# imu_node.net
KiCad netlist of a schematic drawn in EAGLE
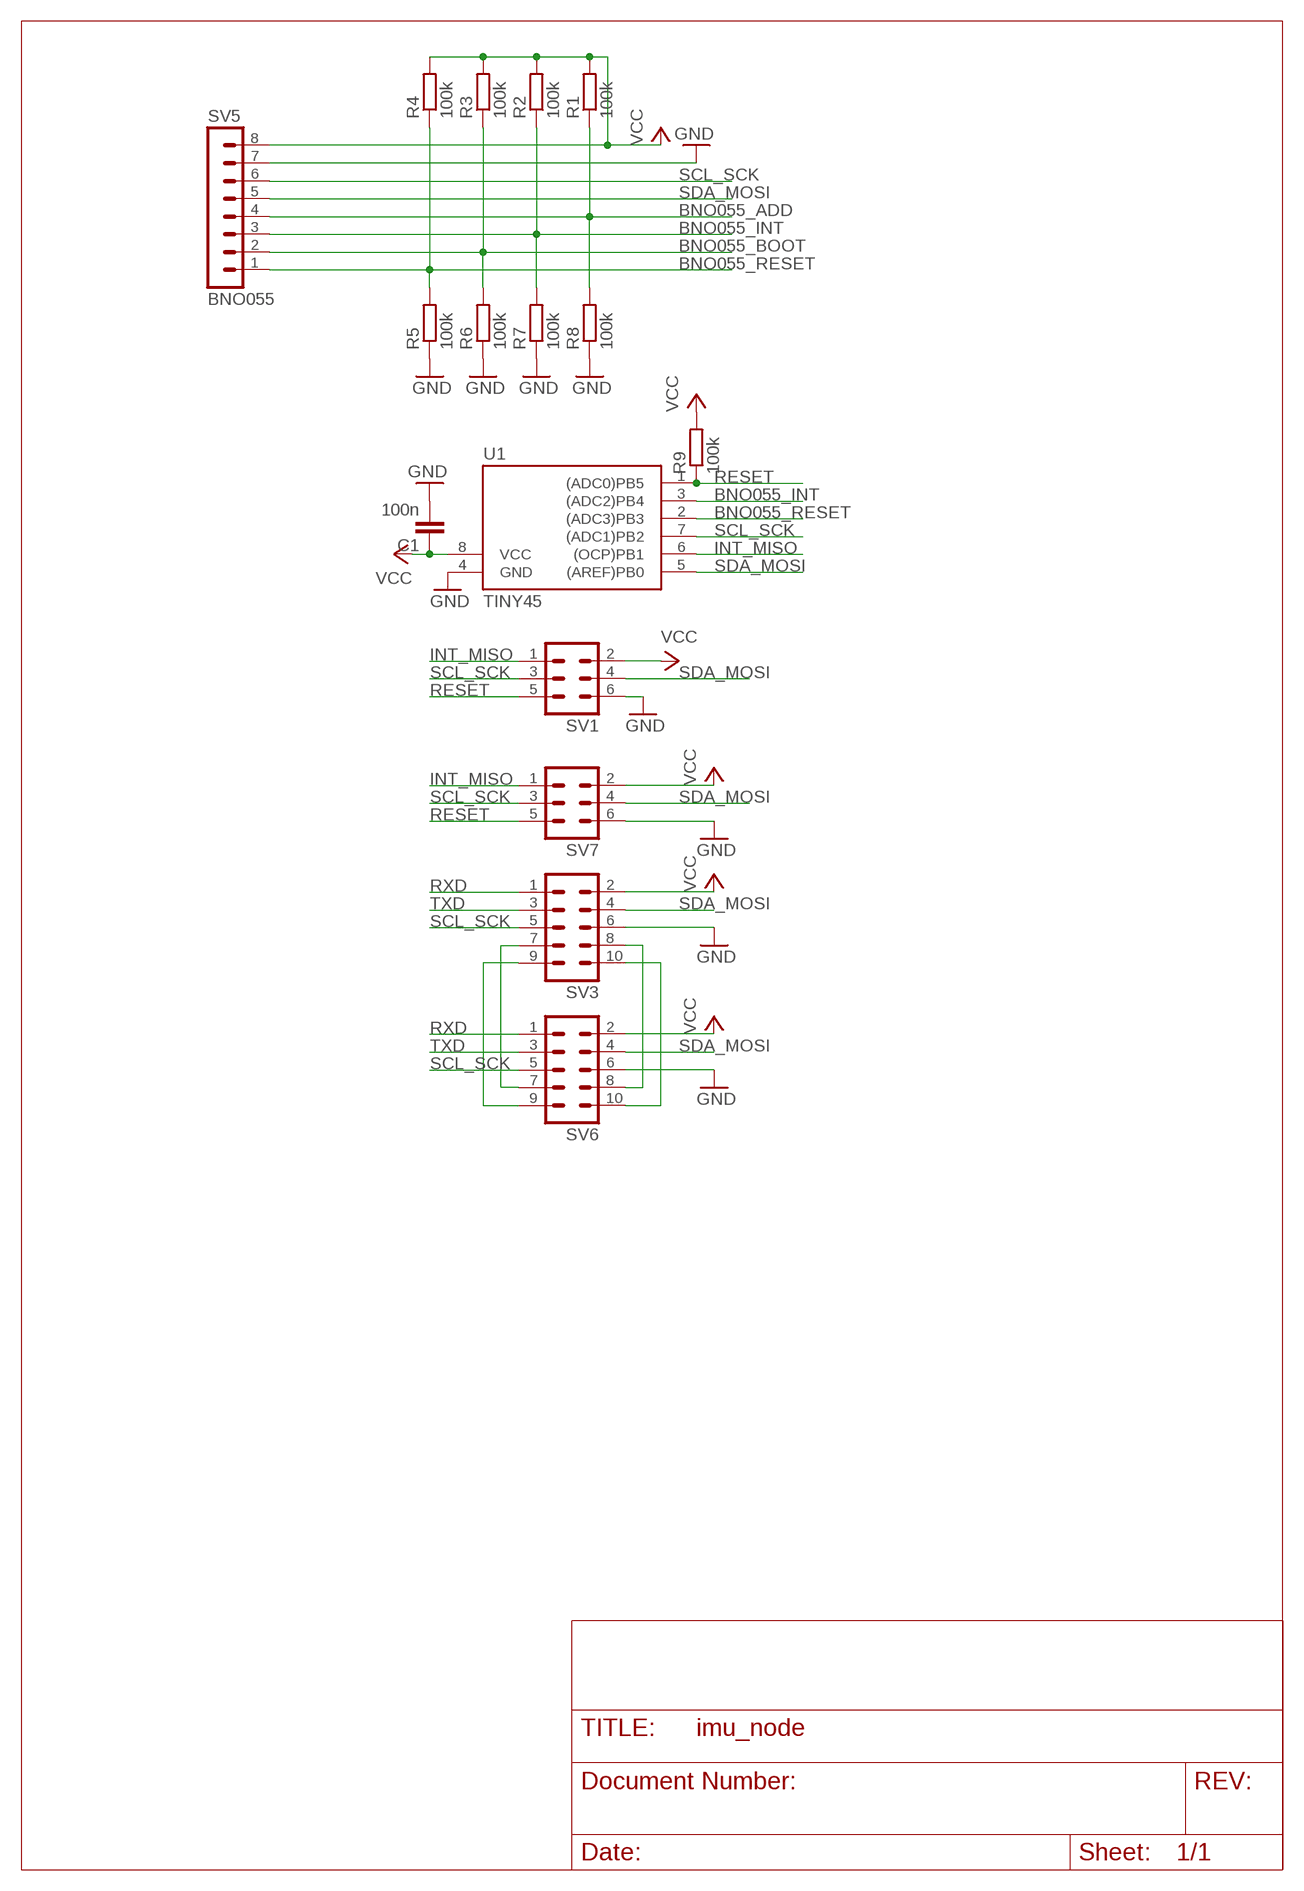
[diagram p0: schematic, sheet 1]

(export (version "E")
  (design (tool "Eeschema 10.0.6"))
  (components
    (comp (ref "C1")
      (value "100n")
      (footprint "eagle-import:C0805")
      (libsource (lib "eagle-import") (part "C-EUC0805"))
    )
    (comp (ref "R1")
      (value "100k")
      (footprint "eagle-import:M0805")
      (libsource (lib "eagle-import") (part "R-EU_M0805"))
    )
    (comp (ref "R2")
      (value "100k")
      (footprint "eagle-import:M0805")
      (libsource (lib "eagle-import") (part "R-EU_M0805"))
    )
    (comp (ref "R3")
      (value "100k")
      (footprint "eagle-import:M0805")
      (libsource (lib "eagle-import") (part "R-EU_M0805"))
    )
    (comp (ref "R4")
      (value "100k")
      (footprint "eagle-import:M0805")
      (libsource (lib "eagle-import") (part "R-EU_M0805"))
    )
    (comp (ref "R5")
      (value "100k")
      (footprint "eagle-import:M0805")
      (libsource (lib "eagle-import") (part "R-EU_M0805"))
    )
    (comp (ref "R6")
      (value "100k")
      (footprint "eagle-import:M0805")
      (libsource (lib "eagle-import") (part "R-EU_M0805"))
    )
    (comp (ref "R7")
      (value "100k")
      (footprint "eagle-import:M0805")
      (libsource (lib "eagle-import") (part "R-EU_M0805"))
    )
    (comp (ref "R8")
      (value "100k")
      (footprint "eagle-import:M0805")
      (libsource (lib "eagle-import") (part "R-EU_M0805"))
    )
    (comp (ref "R9")
      (value "100k")
      (footprint "eagle-import:M0805")
      (libsource (lib "eagle-import") (part "R-EU_M0805"))
    )
    (comp (ref "SV1")
      (value "ML6")
      (footprint "eagle-import:ML6")
      (libsource (lib "eagle-import") (part "ML6"))
    )
    (comp (ref "SV3")
      (value "ML10")
      (footprint "eagle-import:ML10")
      (libsource (lib "eagle-import") (part "ML10"))
    )
    (comp (ref "SV5")
      (value "BNO055")
      (footprint "eagle-import:MA08-1")
      (libsource (lib "eagle-import") (part "MA08-1"))
    )
    (comp (ref "SV6")
      (value "ML10")
      (footprint "eagle-import:ML10")
      (libsource (lib "eagle-import") (part "ML10"))
    )
    (comp (ref "SV7")
      (value "ML6")
      (footprint "eagle-import:ML6")
      (libsource (lib "eagle-import") (part "ML6"))
    )
    (comp (ref "U1")
      (value "TINY45")
      (footprint "eagle-import:SOIC8")
      (libsource (lib "eagle-import") (part "TINY25/45/85-20SU"))
    )
  )
  (nets
    (net (code "1") (name "/BNO055_ADD") (class "Default")
      (node (ref "R1") (pin "1") (pinfunction "1_1") (pintype "passive"))
      (node (ref "R8") (pin "2") (pinfunction "2_2") (pintype "passive"))
      (node (ref "SV5") (pin "4") (pinfunction "4_4") (pintype "passive"))
    )
    (net (code "2") (name "/BNO055_BOOT") (class "Default")
      (node (ref "R3") (pin "1") (pinfunction "1_1") (pintype "passive"))
      (node (ref "R6") (pin "2") (pinfunction "2_2") (pintype "passive"))
      (node (ref "SV5") (pin "2") (pinfunction "2_2") (pintype "passive"))
    )
    (net (code "3") (name "/BNO055_INT") (class "Default")
      (node (ref "R2") (pin "1") (pinfunction "1_1") (pintype "passive"))
      (node (ref "R7") (pin "2") (pinfunction "2_2") (pintype "passive"))
      (node (ref "SV5") (pin "3") (pinfunction "3_3") (pintype "passive"))
      (node (ref "U1") (pin "3") (pinfunction "(ADC2)PB4_3") (pintype "bidirectional"))
    )
    (net (code "4") (name "/BNO055_RESET") (class "Default")
      (node (ref "R4") (pin "1") (pinfunction "1_1") (pintype "passive"))
      (node (ref "R5") (pin "2") (pinfunction "2_2") (pintype "passive"))
      (node (ref "SV5") (pin "1") (pinfunction "1_1") (pintype "passive"))
      (node (ref "U1") (pin "2") (pinfunction "(ADC3)PB3_2") (pintype "bidirectional"))
    )
    (net (code "5") (name "/INT_MISO") (class "Default")
      (node (ref "SV1") (pin "1") (pinfunction "1_1") (pintype "passive"))
      (node (ref "SV7") (pin "1") (pinfunction "1_1") (pintype "passive"))
      (node (ref "U1") (pin "6") (pinfunction "(OCP)PB1_6") (pintype "bidirectional"))
    )
    (net (code "6") (name "/RESET") (class "Default")
      (node (ref "R9") (pin "1") (pinfunction "1_1") (pintype "passive"))
      (node (ref "SV1") (pin "5") (pinfunction "5_5") (pintype "passive"))
      (node (ref "SV7") (pin "5") (pinfunction "5_5") (pintype "passive"))
      (node (ref "U1") (pin "1") (pinfunction "(ADC0)PB5_1") (pintype "bidirectional"))
    )
    (net (code "7") (name "/RXD") (class "Default")
      (node (ref "SV3") (pin "1") (pinfunction "1_1") (pintype "passive"))
      (node (ref "SV6") (pin "1") (pinfunction "1_1") (pintype "passive"))
    )
    (net (code "8") (name "/SCL_SCK") (class "Default")
      (node (ref "SV1") (pin "3") (pinfunction "3_3") (pintype "passive"))
      (node (ref "SV3") (pin "5") (pinfunction "5_5") (pintype "passive"))
      (node (ref "SV5") (pin "6") (pinfunction "6_6") (pintype "passive"))
      (node (ref "SV6") (pin "5") (pinfunction "5_5") (pintype "passive"))
      (node (ref "SV7") (pin "3") (pinfunction "3_3") (pintype "passive"))
      (node (ref "U1") (pin "7") (pinfunction "(ADC1)PB2_7") (pintype "bidirectional"))
    )
    (net (code "9") (name "/SDA_MOSI") (class "Default")
      (node (ref "SV1") (pin "4") (pinfunction "4_4") (pintype "passive"))
      (node (ref "SV3") (pin "4") (pinfunction "4_4") (pintype "passive"))
      (node (ref "SV5") (pin "5") (pinfunction "5_5") (pintype "passive"))
      (node (ref "SV6") (pin "4") (pinfunction "4_4") (pintype "passive"))
      (node (ref "SV7") (pin "4") (pinfunction "4_4") (pintype "passive"))
      (node (ref "U1") (pin "5") (pinfunction "(AREF)PB0_5") (pintype "bidirectional"))
    )
    (net (code "10") (name "/TXD") (class "Default")
      (node (ref "SV3") (pin "3") (pinfunction "3_3") (pintype "passive"))
      (node (ref "SV6") (pin "3") (pinfunction "3_3") (pintype "passive"))
    )
    (net (code "11") (name "GND") (class "Default")
      (node (ref "C1") (pin "2") (pinfunction "2_2") (pintype "passive"))
      (node (ref "R5") (pin "1") (pinfunction "1_1") (pintype "passive"))
      (node (ref "R6") (pin "1") (pinfunction "1_1") (pintype "passive"))
      (node (ref "R7") (pin "1") (pinfunction "1_1") (pintype "passive"))
      (node (ref "R8") (pin "1") (pinfunction "1_1") (pintype "passive"))
      (node (ref "SV1") (pin "6") (pinfunction "6_6") (pintype "passive"))
      (node (ref "SV3") (pin "6") (pinfunction "6_6") (pintype "passive"))
      (node (ref "SV5") (pin "7") (pinfunction "7_7") (pintype "passive"))
      (node (ref "SV6") (pin "6") (pinfunction "6_6") (pintype "passive"))
      (node (ref "SV7") (pin "6") (pinfunction "6_6") (pintype "passive"))
      (node (ref "U1") (pin "4") (pinfunction "GND_4") (pintype "power_in"))
    )
    (net (code "12") (name "Net-(SV3-Pad7)") (class "Default")
      (node (ref "SV3") (pin "7") (pinfunction "7_7") (pintype "passive"))
      (node (ref "SV6") (pin "7") (pinfunction "7_7") (pintype "passive"))
    )
    (net (code "13") (name "Net-(SV3-Pad8)") (class "Default")
      (node (ref "SV3") (pin "8") (pinfunction "8_8") (pintype "passive"))
      (node (ref "SV6") (pin "8") (pinfunction "8_8") (pintype "passive"))
    )
    (net (code "14") (name "Net-(SV3-Pad9)") (class "Default")
      (node (ref "SV3") (pin "9") (pinfunction "9_9") (pintype "passive"))
      (node (ref "SV6") (pin "9") (pinfunction "9_9") (pintype "passive"))
    )
    (net (code "15") (name "Net-(SV3-Pad10)") (class "Default")
      (node (ref "SV3") (pin "10") (pinfunction "10_10") (pintype "passive"))
      (node (ref "SV6") (pin "10") (pinfunction "10_10") (pintype "passive"))
    )
    (net (code "16") (name "VCC") (class "Default")
      (node (ref "C1") (pin "1") (pinfunction "1_1") (pintype "passive"))
      (node (ref "R1") (pin "2") (pinfunction "2_2") (pintype "passive"))
      (node (ref "R2") (pin "2") (pinfunction "2_2") (pintype "passive"))
      (node (ref "R3") (pin "2") (pinfunction "2_2") (pintype "passive"))
      (node (ref "R4") (pin "2") (pinfunction "2_2") (pintype "passive"))
      (node (ref "R9") (pin "2") (pinfunction "2_2") (pintype "passive"))
      (node (ref "SV1") (pin "2") (pinfunction "2_2") (pintype "passive"))
      (node (ref "SV3") (pin "2") (pinfunction "2_2") (pintype "passive"))
      (node (ref "SV5") (pin "8") (pinfunction "8_8") (pintype "passive"))
      (node (ref "SV6") (pin "2") (pinfunction "2_2") (pintype "passive"))
      (node (ref "SV7") (pin "2") (pinfunction "2_2") (pintype "passive"))
      (node (ref "U1") (pin "8") (pinfunction "VCC_8") (pintype "power_in"))
    )
  )
)
